# P1R3.net
KiCad netlist of a schematic drawn in EAGLE
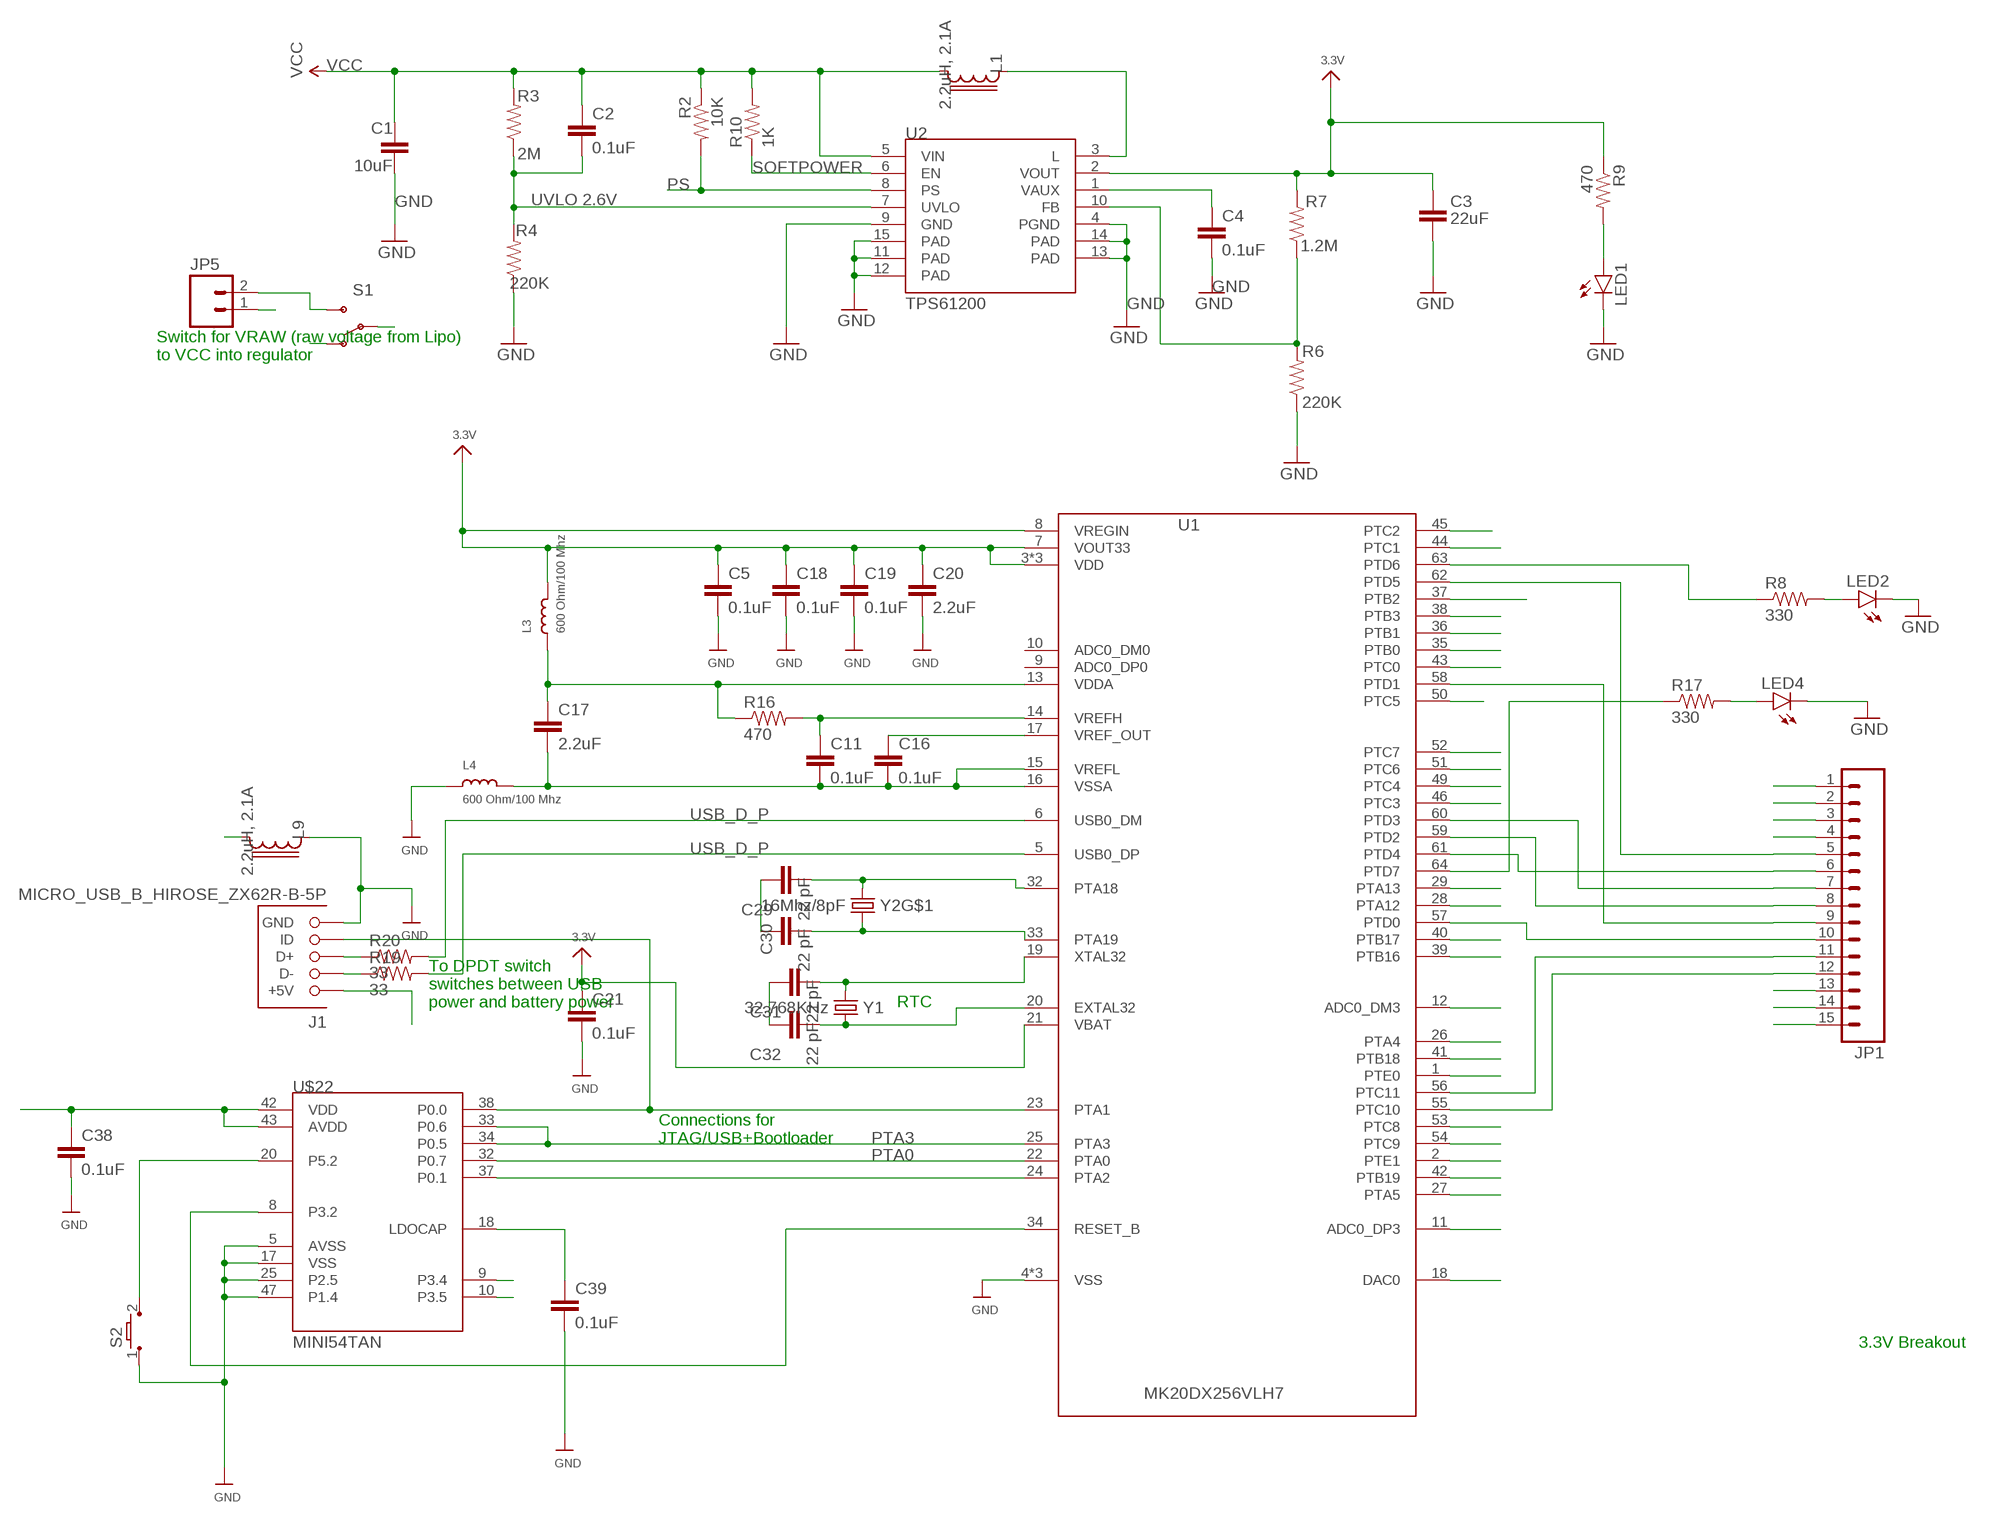
[diagram p0: schematic, sheet 1]
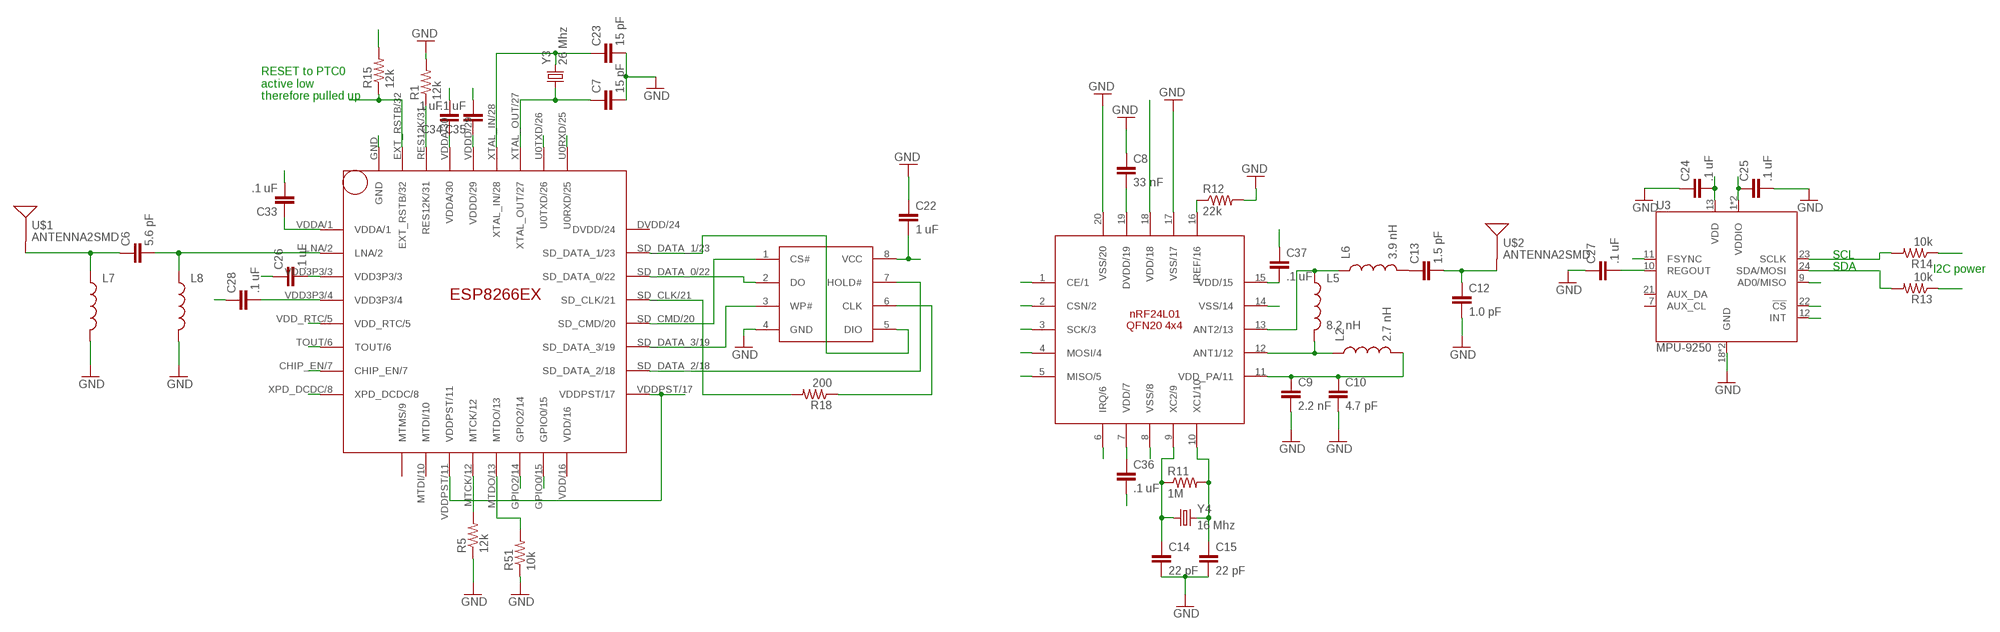
[diagram p1: schematic, sheet 2]

(export (version "E")
  (design (tool "Eeschema 10.0.6"))
  (components
    (comp (ref "C1")
      (value "10uF")
      (footprint "eagle-import:0603-CAP")
      (fields (field (name "MF") "Murata") (field (name "MPN") "GRM188R60J106ME47D"))
      (libsource (lib "eagle-import") (part "CAPACITOR-10UF"))
    )
    (comp (ref "C2")
      (value "0.1uF")
      (footprint "eagle-import:0603-CAP")
      (fields (field (name "MF") "Kemet") (field (name "MPN") "C0603C104J3RACTU"))
      (libsource (lib "eagle-import") (part "CAPACITOR-0.1UF"))
    )
    (comp (ref "C3")
      (value "22uF")
      (footprint "eagle-import:0603-CAP")
      (fields (field (name "MF") "Murata") (field (name "MPN") "GRM188R60J226MEA0D"))
      (libsource (lib "eagle-import") (part "CAPACITOR-22UF"))
    )
    (comp (ref "C4")
      (value "0.1uF")
      (footprint "eagle-import:0603-CAP")
      (fields (field (name "MF") "Kemet") (field (name "MPN") "C0603C104J3RACTU"))
      (libsource (lib "eagle-import") (part "CAPACITOR-0.1UF"))
    )
    (comp (ref "C5")
      (value "0.1uF")
      (footprint "eagle-import:0603-CAP")
      (fields (field (name "MF") "Kemet") (field (name "MPN") "C0603C104J3RACTU"))
      (libsource (lib "eagle-import") (part "CAPACITOR-0.1UF"))
    )
    (comp (ref "C11")
      (value "0.1uF")
      (footprint "eagle-import:0603-CAP")
      (fields (field (name "MF") "Kemet") (field (name "MPN") "C0603C104J3RACTU"))
      (libsource (lib "eagle-import") (part "CAPACITOR-0.1UF"))
    )
    (comp (ref "C16")
      (value "0.1uF")
      (footprint "eagle-import:0603-CAP")
      (fields (field (name "MF") "Kemet") (field (name "MPN") "C0603C104J3RACTU"))
      (libsource (lib "eagle-import") (part "CAPACITOR-0.1UF"))
    )
    (comp (ref "C17")
      (value "2.2uF")
      (footprint "eagle-import:0603-CAP")
      (fields (field (name "MF") "Kemet") (field (name "MPN") "C0603C225K4PACTU"))
      (libsource (lib "eagle-import") (part "CAPACITOR-2.2UF"))
    )
    (comp (ref "C18")
      (value "0.1uF")
      (footprint "eagle-import:0603-CAP")
      (fields (field (name "MF") "Kemet") (field (name "MPN") "C0603C104J3RACTU"))
      (libsource (lib "eagle-import") (part "CAPACITOR-0.1UF"))
    )
    (comp (ref "C19")
      (value "0.1uF")
      (footprint "eagle-import:0603-CAP")
      (fields (field (name "MF") "Kemet") (field (name "MPN") "C0603C104J3RACTU"))
      (libsource (lib "eagle-import") (part "CAPACITOR-0.1UF"))
    )
    (comp (ref "C20")
      (value "2.2uF")
      (footprint "eagle-import:0603-CAP")
      (fields (field (name "MF") "Kemet") (field (name "MPN") "C0603C225K4PACTU"))
      (libsource (lib "eagle-import") (part "CAPACITOR-2.2UF"))
    )
    (comp (ref "C21")
      (value "0.1uF")
      (footprint "eagle-import:0603-CAP")
      (fields (field (name "MF") "Kemet") (field (name "MPN") "C0603C104J3RACTU"))
      (libsource (lib "eagle-import") (part "CAPACITOR-0.1UF"))
    )
    (comp (ref "C29")
      (value "22 pF")
      (footprint "eagle-import:0603-CAP")
      (fields (field (name "MF") "Murata") (field (name "MPN") "GRM188R60J106ME47D"))
      (libsource (lib "eagle-import") (part "CAPACITOR-10UF"))
    )
    (comp (ref "C30")
      (value "22 pF")
      (footprint "eagle-import:0603-CAP")
      (fields (field (name "MF") "Murata") (field (name "MPN") "GRM188R60J106ME47D"))
      (libsource (lib "eagle-import") (part "CAPACITOR-10UF"))
    )
    (comp (ref "C31")
      (value "22 pF")
      (footprint "eagle-import:0603-CAP")
      (fields (field (name "MF") "Murata") (field (name "MPN") "GRM188R60J106ME47D"))
      (libsource (lib "eagle-import") (part "CAPACITOR-10UF"))
    )
    (comp (ref "C32")
      (value "22 pF")
      (footprint "eagle-import:0603-CAP")
      (fields (field (name "MF") "Murata") (field (name "MPN") "GRM188R60J106ME47D"))
      (libsource (lib "eagle-import") (part "CAPACITOR-10UF"))
    )
    (comp (ref "C38")
      (value "0.1uF")
      (footprint "eagle-import:0603-CAP")
      (fields (field (name "MF") "Kemet") (field (name "MPN") "C0603C104J3RACTU"))
      (libsource (lib "eagle-import") (part "CAPACITOR-0.1UF"))
    )
    (comp (ref "C39")
      (value "0.1uF")
      (footprint "eagle-import:0603-CAP")
      (fields (field (name "MF") "Kemet") (field (name "MPN") "C0603C104J3RACTU"))
      (libsource (lib "eagle-import") (part "CAPACITOR-0.1UF"))
    )
    (comp (ref "J1")
      (value "MICRO_USB_B_HIROSE_ZX62R-B-5P")
      (footprint "eagle-import:USB_MICRO_B-HIROSE-ZX62R-B-5P")
      (libsource (lib "eagle-import") (part "MICRO_USB_B_HIROSE_ZX62R-B-5P"))
    )
    (comp (ref "JP1")
      (value "M15")
      (footprint "eagle-import:1X15")
      (libsource (lib "eagle-import") (part "M15"))
    )
    (comp (ref "JP5")
      (value "M02PTH")
      (footprint "eagle-import:1X02")
      (libsource (lib "eagle-import") (part "M02PTH"))
    )
    (comp (ref "L1")
      (value "2.2uH, 2.1A")
      (footprint "eagle-import:LPS3015")
      (fields (field (name "MF") "Coilcraft") (field (name "MPN") "LPS3015-222MRB"))
      (libsource (lib "eagle-import") (part "LPS30152.2UH"))
    )
    (comp (ref "L3")
      (value "600 Ohm/100 Mhz")
      (footprint "eagle-import:0805")
      (fields (field (name "MF") "Taiyo Yuden") (field (name "MPN") "BK2125HM601-T"))
      (libsource (lib "eagle-import") (part "INDUCTOR-BK2125HM601-T"))
    )
    (comp (ref "L4")
      (value "600 Ohm/100 Mhz")
      (footprint "eagle-import:0805")
      (fields (field (name "MF") "Taiyo Yuden") (field (name "MPN") "BK2125HM601-T"))
      (libsource (lib "eagle-import") (part "INDUCTOR-BK2125HM601-T"))
    )
    (comp (ref "L9")
      (value "2.2uH, 2.1A")
      (footprint "eagle-import:LPS3015")
      (fields (field (name "MF") "Coilcraft") (field (name "MPN") "LPS3015-222MRB"))
      (libsource (lib "eagle-import") (part "LPS30152.2UH"))
    )
    (comp (ref "LED1")
      (value "LED-GREEN")
      (footprint "eagle-import:LED-0603")
      (fields (field (name "MF") "Avago") (field (name "MPN") "HSMG-C190"))
      (libsource (lib "eagle-import") (part "LED-GREEN"))
    )
    (comp (ref "LED2")
      (value "LED-GREEN")
      (footprint "eagle-import:LED-0603")
      (fields (field (name "MF") "Avago") (field (name "MPN") "HSMG-C190"))
      (libsource (lib "eagle-import") (part "LED-GREEN"))
    )
    (comp (ref "LED4")
      (value "LED-GREEN")
      (footprint "eagle-import:LED-0603")
      (fields (field (name "MF") "Avago") (field (name "MPN") "HSMG-C190"))
      (libsource (lib "eagle-import") (part "LED-GREEN"))
    )
    (comp (ref "R2")
      (value "10K")
      (footprint "eagle-import:0603-RES")
      (fields (field (name "MF") "Panasonic") (field (name "MPN") "ERJ-3GEYJ103V"))
      (libsource (lib "eagle-import") (part "RESISTOR-10K"))
    )
    (comp (ref "R3")
      (value "2M")
      (footprint "eagle-import:0603-RES")
      (fields (field (name "MF") "Panasonic") (field (name "MPN") "ERJ-3GEYJ205V"))
      (libsource (lib "eagle-import") (part "RESISTOR-2M"))
    )
    (comp (ref "R4")
      (value "220K")
      (footprint "eagle-import:0603-RES")
      (fields (field (name "MF") "Panasonic") (field (name "MPN") "ERJ-3GEYJ224V"))
      (libsource (lib "eagle-import") (part "RESISTOR-220K"))
    )
    (comp (ref "R6")
      (value "220K")
      (footprint "eagle-import:0603-RES")
      (fields (field (name "MF") "Panasonic") (field (name "MPN") "ERJ-3GEYJ224V"))
      (libsource (lib "eagle-import") (part "RESISTOR-220K"))
    )
    (comp (ref "R7")
      (value "1.2M")
      (footprint "eagle-import:0603-RES")
      (fields (field (name "MF") "Panasonic") (field (name "MPN") "ERJ-3GEYJ125V"))
      (libsource (lib "eagle-import") (part "RESISTOR-1.2M"))
    )
    (comp (ref "R8")
      (value "330")
      (footprint "eagle-import:0603-RES")
      (fields (field (name "MF") "Panasonic") (field (name "MPN") "ERJ-3GEYJ471V"))
      (libsource (lib "eagle-import") (part "RESISTOR-470"))
    )
    (comp (ref "R9")
      (value "470")
      (footprint "eagle-import:0603-RES")
      (fields (field (name "MF") "Panasonic") (field (name "MPN") "ERJ-3GEYJ471V"))
      (libsource (lib "eagle-import") (part "RESISTOR-470"))
    )
    (comp (ref "R10")
      (value "1K")
      (footprint "eagle-import:0603-RES")
      (fields (field (name "MF") "Panasonic") (field (name "MPN") "ERJ-3GEYJ102V"))
      (libsource (lib "eagle-import") (part "RESISTOR-1K"))
    )
    (comp (ref "R16")
      (value "470")
      (footprint "eagle-import:0603-RES")
      (fields (field (name "MF") "Panasonic") (field (name "MPN") "ERJ-3GEYJ471V"))
      (libsource (lib "eagle-import") (part "RESISTOR-470"))
    )
    (comp (ref "R17")
      (value "330")
      (footprint "eagle-import:0603-RES")
      (fields (field (name "MF") "Panasonic") (field (name "MPN") "ERJ-3GEYJ471V"))
      (libsource (lib "eagle-import") (part "RESISTOR-470"))
    )
    (comp (ref "R19")
      (value "33")
      (footprint "eagle-import:0402-RES")
      (libsource (lib "eagle-import") (part "RESISTOR0402-RES"))
    )
    (comp (ref "R20")
      (value "33")
      (footprint "eagle-import:0402-RES")
      (libsource (lib "eagle-import") (part "RESISTOR0402-RES"))
    )
    (comp (ref "S1")
      (value "SWITCH-SPDT-SMD-A")
      (footprint "eagle-import:SWITCH-SPST-SMD-A")
      (libsource (lib "eagle-import") (part "SWITCH-SPDT-SMD-A"))
    )
    (comp (ref "S2")
      (value "TL3302-G")
      (footprint "eagle-import:TL3302_GULL_WING")
      (libsource (lib "eagle-import") (part "TL3302-G"))
    )
    (comp (ref "U$22")
      (value "MINI54TAN")
      (footprint "eagle-import:MINI54TAN")
      (libsource (lib "eagle-import") (part "MINI54TAN"))
    )
    (comp (ref "U1")
      (value "MK20DX256VLH7")
      (footprint "eagle-import:MK20DX256VLH7")
      (fields (field (name "MF") "Freescale"))
      (libsource (lib "eagle-import") (part "MK20DX256VLH7"))
    )
    (comp (ref "U2")
      (value "TPS61200")
      (footprint "eagle-import:QFN-10_PAD")
      (fields (field (name "MF") "Texas Instruments") (field (name "MPN") "TPS61200DRCR"))
      (libsource (lib "eagle-import") (part "TPS61200"))
    )
    (comp (ref "Y1")
      (value "32.768KHz")
      (footprint "eagle-import:CRYSTAL-TXC-7A")
      (fields (field (name "MF") "Epson Timing") (field (name "MPN") "FC-255 32.7680K-A3"))
      (libsource (lib "eagle-import") (part "CRYSTAL/32.768KHZ/SMD-TXC_7A"))
    )
    (comp (ref "Y2")
      (value "16Mhz/8pF")
      (footprint "eagle-import:CRYSTAL-SMD-5X3")
      (fields (field (name "MF") "ECS") (field (name "MPN") "ECS-160-8-30B-CKM"))
      (libsource (lib "eagle-import") (part "CRYSTAL/SMD-5X3-GND16MHZ/8PF"))
    )
    (comp (ref "C6")
      (value "5.6 pF")
      (footprint "eagle-import:0603-CAP")
      (libsource (lib "eagle-import") (part "CAP0603-CAP"))
    )
    (comp (ref "C7")
      (value "15 pF")
      (footprint "eagle-import:0603-CAP")
      (libsource (lib "eagle-import") (part "CAP0603-CAP"))
    )
    (comp (ref "C8")
      (value "33 nF")
      (footprint "eagle-import:0603-CAP")
      (libsource (lib "eagle-import") (part "CAP0603-CAP"))
    )
    (comp (ref "C9")
      (value "2.2 nF")
      (footprint "eagle-import:0603-CAP")
      (libsource (lib "eagle-import") (part "CAP0603-CAP"))
    )
    (comp (ref "C10")
      (value "4.7 pF")
      (footprint "eagle-import:0603-CAP")
      (libsource (lib "eagle-import") (part "CAP0603-CAP"))
    )
    (comp (ref "C12")
      (value "1.0 pF")
      (footprint "eagle-import:0603-CAP")
      (libsource (lib "eagle-import") (part "CAP0603-CAP"))
    )
    (comp (ref "C13")
      (value "1.5 pF")
      (footprint "eagle-import:0603-CAP")
      (libsource (lib "eagle-import") (part "CAP0603-CAP"))
    )
    (comp (ref "C14")
      (value "22 pF")
      (footprint "eagle-import:0603-CAP")
      (libsource (lib "eagle-import") (part "CAP0603-CAP"))
    )
    (comp (ref "C15")
      (value "22 pF")
      (footprint "eagle-import:0603-CAP")
      (libsource (lib "eagle-import") (part "CAP0603-CAP"))
    )
    (comp (ref "C22")
      (value "1 uF")
      (footprint "eagle-import:0603-CAP")
      (libsource (lib "eagle-import") (part "CAP0603-CAP"))
    )
    (comp (ref "C23")
      (value "15 pF")
      (footprint "eagle-import:0603-CAP")
      (libsource (lib "eagle-import") (part "CAP0603-CAP"))
    )
    (comp (ref "C24")
      (value ".1 uF")
      (footprint "eagle-import:0603-CAP")
      (libsource (lib "eagle-import") (part "CAP0603-CAP"))
    )
    (comp (ref "C25")
      (value ".1 uF")
      (footprint "eagle-import:0603-CAP")
      (libsource (lib "eagle-import") (part "CAP0603-CAP"))
    )
    (comp (ref "C26")
      (value ".1 uF")
      (footprint "eagle-import:0603-CAP")
      (libsource (lib "eagle-import") (part "CAP0603-CAP"))
    )
    (comp (ref "C27")
      (value ".1 uF")
      (footprint "eagle-import:0603-CAP")
      (libsource (lib "eagle-import") (part "CAP0603-CAP"))
    )
    (comp (ref "C28")
      (value ".1 uF")
      (footprint "eagle-import:0603-CAP")
      (libsource (lib "eagle-import") (part "CAP0603-CAP"))
    )
    (comp (ref "C33")
      (value ".1 uF")
      (footprint "eagle-import:0603-CAP")
      (libsource (lib "eagle-import") (part "CAP0603-CAP"))
    )
    (comp (ref "C34")
      (value ".1 uF")
      (footprint "eagle-import:0603-CAP")
      (libsource (lib "eagle-import") (part "CAP0603-CAP"))
    )
    (comp (ref "C35")
      (value ".1 uF")
      (footprint "eagle-import:0603-CAP")
      (libsource (lib "eagle-import") (part "CAP0603-CAP"))
    )
    (comp (ref "C36")
      (value ".1 uF")
      (footprint "eagle-import:0603-CAP")
      (libsource (lib "eagle-import") (part "CAP0603-CAP"))
    )
    (comp (ref "C37")
      (value ".1 uF")
      (footprint "eagle-import:0603-CAP")
      (libsource (lib "eagle-import") (part "CAP0603-CAP"))
    )
    (comp (ref "L2")
      (value "2.7 nH")
      (footprint "eagle-import:C0402")
      (libsource (lib "eagle-import") (part "INDUCTOR0402"))
    )
    (comp (ref "L5")
      (value "8.2 nH")
      (footprint "eagle-import:C0402")
      (libsource (lib "eagle-import") (part "INDUCTOR0402"))
    )
    (comp (ref "L6")
      (value "3.9 nH")
      (footprint "eagle-import:C0402")
      (libsource (lib "eagle-import") (part "INDUCTOR0402"))
    )
    (comp (ref "L7")
      (value "INDUCTOR30OHM,1.8A")
      (footprint "eagle-import:0603")
      (libsource (lib "eagle-import") (part "INDUCTOR30OHM,1.8A"))
    )
    (comp (ref "L8")
      (value "INDUCTOR30OHM,1.8A")
      (footprint "eagle-import:0603")
      (libsource (lib "eagle-import") (part "INDUCTOR30OHM,1.8A"))
    )
    (comp (ref "R1")
      (value "12k")
      (footprint "eagle-import:0603-RES")
      (libsource (lib "eagle-import") (part "SparkFun-Resistors_RESISTOR0603-RES"))
    )
    (comp (ref "R5")
      (value "12k")
      (footprint "eagle-import:0603-RES")
      (libsource (lib "eagle-import") (part "SparkFun-Resistors_RESISTOR0603-RES"))
    )
    (comp (ref "R11")
      (value "1M")
      (footprint "eagle-import:0603-RES")
      (libsource (lib "eagle-import") (part "SparkFun-Resistors_RESISTOR0603-RES"))
    )
    (comp (ref "R12")
      (value "22k")
      (footprint "eagle-import:0603-RES")
      (libsource (lib "eagle-import") (part "SparkFun-Resistors_RESISTOR0603-RES"))
    )
    (comp (ref "R13")
      (value "10k")
      (footprint "eagle-import:0603-RES")
      (libsource (lib "eagle-import") (part "SparkFun-Resistors_RESISTOR0603-RES"))
    )
    (comp (ref "R14")
      (value "10k")
      (footprint "eagle-import:0603-RES")
      (libsource (lib "eagle-import") (part "SparkFun-Resistors_RESISTOR0603-RES"))
    )
    (comp (ref "R15")
      (value "12k")
      (footprint "eagle-import:0603-RES")
      (libsource (lib "eagle-import") (part "SparkFun-Resistors_RESISTOR0603-RES"))
    )
    (comp (ref "R18")
      (value "200")
      (footprint "eagle-import:0603-RES")
      (libsource (lib "eagle-import") (part "SparkFun-Resistors_RESISTOR0603-RES"))
    )
    (comp (ref "R51")
      (value "10k")
      (footprint "eagle-import:0603-RES")
      (libsource (lib "eagle-import") (part "SparkFun-Resistors_RESISTOR0603-RES"))
    )
    (comp (ref "U$1")
      (value "ANTENNA2SMD")
      (footprint "eagle-import:ANTENNA-CHIP2")
      (libsource (lib "eagle-import") (part "ANTENNA2SMD"))
    )
    (comp (ref "U$2")
      (value "ANTENNA2SMD")
      (footprint "eagle-import:ANTENNA-CHIP2")
      (libsource (lib "eagle-import") (part "ANTENNA2SMD"))
    )
    (comp (ref "U$3")
      (value "25Q40")
      (footprint "eagle-import:SOP8")
      (libsource (lib "eagle-import") (part "25Q40"))
    )
    (comp (ref "U$4")
      (value "NRF24L01")
      (footprint "eagle-import:QFN20(4X4)")
      (libsource (lib "eagle-import") (part "NRF24L01"))
    )
    (comp (ref "U$6")
      (value "ESP8266EX")
      (footprint "eagle-import:QFN32")
      (libsource (lib "eagle-import") (part "ESP8266EX"))
    )
    (comp (ref "U3")
      (value "MPU-9250")
      (footprint "eagle-import:QFN-24_3MM")
      (libsource (lib "eagle-import") (part "MPU-9250"))
    )
    (comp (ref "Y3")
      (value "26 Mhz")
      (footprint "eagle-import:CRYSTAL-SMD-5X3")
      (libsource (lib "eagle-import") (part "CRYSTAL5X3"))
    )
    (comp (ref "Y4")
      (value "16 Mhz")
      (footprint "eagle-import:CRYSTAL-SMD-5X3")
      (libsource (lib "eagle-import") (part "CRYSTAL5X3"))
    )
  )
  (nets
    (net (code "1") (name "3.3V") (class "Default")
      (node (ref "C18") (pin "1") (pinfunction "1_1") (pintype "passive"))
      (node (ref "C19") (pin "1") (pinfunction "1_1") (pintype "passive"))
      (node (ref "C20") (pin "1") (pinfunction "1_1") (pintype "passive"))
      (node (ref "C21") (pin "1") (pinfunction "1_1") (pintype "passive"))
      (node (ref "C22") (pin "2") (pinfunction "2_2") (pintype "passive"))
      (node (ref "C24") (pin "2") (pinfunction "2_2") (pintype "passive"))
      (node (ref "C25") (pin "1") (pinfunction "1_1") (pintype "passive"))
      (node (ref "C26") (pin "2") (pinfunction "2_2") (pintype "passive"))
      (node (ref "C28") (pin "2") (pinfunction "2_2") (pintype "passive"))
      (node (ref "C3") (pin "1") (pinfunction "1_1") (pintype "passive"))
      (node (ref "C33") (pin "1") (pinfunction "1_1") (pintype "passive"))
      (node (ref "C34") (pin "1") (pinfunction "1_1") (pintype "passive"))
      (node (ref "C35") (pin "1") (pinfunction "1_1") (pintype "passive"))
      (node (ref "C36") (pin "1") (pinfunction "1_1") (pintype "passive"))
      (node (ref "C37") (pin "2") (pinfunction "2_2") (pintype "passive"))
      (node (ref "C38") (pin "1") (pinfunction "1_1") (pintype "passive"))
      (node (ref "C5") (pin "1") (pinfunction "1_1") (pintype "passive"))
      (node (ref "JP1") (pin "13") (pinfunction "13_13") (pintype "passive"))
      (node (ref "JP1") (pin "14") (pinfunction "14_14") (pintype "passive"))
      (node (ref "JP1") (pin "15") (pinfunction "15_15") (pintype "passive"))
      (node (ref "L3") (pin "2") (pinfunction "2_2") (pintype "passive"))
      (node (ref "R13") (pin "1") (pinfunction "1_1") (pintype "passive"))
      (node (ref "R14") (pin "1") (pinfunction "1_1") (pintype "passive"))
      (node (ref "R15") (pin "2") (pinfunction "2_2") (pintype "passive"))
      (node (ref "R7") (pin "2") (pinfunction "2_2") (pintype "passive"))
      (node (ref "R9") (pin "1") (pinfunction "1_1") (pintype "passive"))
      (node (ref "U$22") (pin "42") (pinfunction "VDD_42") (pintype "bidirectional"))
      (node (ref "U$22") (pin "43") (pinfunction "AVDD_43") (pintype "bidirectional"))
      (node (ref "U$3") (pin "8") (pinfunction "VCC_8") (pintype "bidirectional"))
      (node (ref "U$4") (pin "15") (pinfunction "VDD/15_15") (pintype "bidirectional"))
      (node (ref "U$4") (pin "18") (pinfunction "VDD/18_18") (pintype "bidirectional"))
      (node (ref "U$4") (pin "7") (pinfunction "VDD/7_7") (pintype "bidirectional"))
      (node (ref "U$6") (pin "VDD3P3/3") (pinfunction "VDD3P3/3_VDD3P3/3") (pintype "bidirectional"))
      (node (ref "U$6") (pin "VDD3P3/4") (pinfunction "VDD3P3/4_VDD3P3/4") (pintype "bidirectional"))
      (node (ref "U$6") (pin "VDDA/1") (pinfunction "VDDA/1_VDDA/1") (pintype "bidirectional"))
      (node (ref "U$6") (pin "VDDA/30") (pinfunction "VDDA/30_VDDA/30") (pintype "bidirectional"))
      (node (ref "U$6") (pin "VDDD/29") (pinfunction "VDDD/29_VDDD/29") (pintype "bidirectional"))
      (node (ref "U$6") (pin "VDDPST/11") (pinfunction "VDDPST/11_VDDPST/11") (pintype "bidirectional"))
      (node (ref "U$6") (pin "VDDPST/17") (pinfunction "VDDPST/17_VDDPST/17") (pintype "bidirectional"))
      (node (ref "U1") (pin "21") (pinfunction "VBAT_21") (pintype "bidirectional"))
      (node (ref "U1") (pin "3") (pinfunction "VDD_3") (pintype "bidirectional"))
      (node (ref "U1") (pin "30") (pinfunction "VDD_30") (pintype "bidirectional"))
      (node (ref "U1") (pin "48") (pinfunction "VDD_48") (pintype "bidirectional"))
      (node (ref "U1") (pin "7") (pinfunction "VOUT33_7") (pintype "bidirectional"))
      (node (ref "U1") (pin "8") (pinfunction "VREGIN_8") (pintype "bidirectional"))
      (node (ref "U2") (pin "2") (pinfunction "VOUT_2") (pintype "passive"))
      (node (ref "U3") (pin "1") (pinfunction "VDDIO_1") (pintype "bidirectional"))
      (node (ref "U3") (pin "13") (pinfunction "VDD_13") (pintype "bidirectional"))
      (node (ref "U3") (pin "22") (pinfunction "~{CS}_22") (pintype "bidirectional"))
      (node (ref "U3") (pin "8") (pinfunction "VDDIO_8") (pintype "bidirectional"))
    )
    (net (code "2") (name "AD0") (class "Default")
      (node (ref "U1") (pin "45") (pinfunction "PTC2_45") (pintype "bidirectional"))
      (node (ref "U3") (pin "9") (pinfunction "AD0/MISO_9") (pintype "bidirectional"))
    )
    (net (code "3") (name "GND") (class "Default")
      (node (ref "C1") (pin "2") (pinfunction "2_2") (pintype "passive"))
      (node (ref "C10") (pin "2") (pinfunction "2_2") (pintype "passive"))
      (node (ref "C12") (pin "2") (pinfunction "2_2") (pintype "passive"))
      (node (ref "C14") (pin "2") (pinfunction "2_2") (pintype "passive"))
      (node (ref "C15") (pin "2") (pinfunction "2_2") (pintype "passive"))
      (node (ref "C18") (pin "2") (pinfunction "2_2") (pintype "passive"))
      (node (ref "C19") (pin "2") (pinfunction "2_2") (pintype "passive"))
      (node (ref "C20") (pin "2") (pinfunction "2_2") (pintype "passive"))
      (node (ref "C21") (pin "2") (pinfunction "2_2") (pintype "passive"))
      (node (ref "C22") (pin "1") (pinfunction "1_1") (pintype "passive"))
      (node (ref "C23") (pin "2") (pinfunction "2_2") (pintype "passive"))
      (node (ref "C24") (pin "1") (pinfunction "1_1") (pintype "passive"))
      (node (ref "C25") (pin "2") (pinfunction "2_2") (pintype "passive"))
      (node (ref "C26") (pin "1") (pinfunction "1_1") (pintype "passive"))
      (node (ref "C27") (pin "1") (pinfunction "1_1") (pintype "passive"))
      (node (ref "C28") (pin "1") (pinfunction "1_1") (pintype "passive"))
      (node (ref "C29") (pin "1") (pinfunction "1_1") (pintype "passive"))
      (node (ref "C3") (pin "2") (pinfunction "2_2") (pintype "passive"))
      (node (ref "C30") (pin "1") (pinfunction "1_1") (pintype "passive"))
      (node (ref "C31") (pin "1") (pinfunction "1_1") (pintype "passive"))
      (node (ref "C32") (pin "1") (pinfunction "1_1") (pintype "passive"))
      (node (ref "C33") (pin "2") (pinfunction "2_2") (pintype "passive"))
      (node (ref "C34") (pin "2") (pinfunction "2_2") (pintype "passive"))
      (node (ref "C35") (pin "2") (pinfunction "2_2") (pintype "passive"))
      (node (ref "C36") (pin "2") (pinfunction "2_2") (pintype "passive"))
      (node (ref "C37") (pin "1") (pinfunction "1_1") (pintype "passive"))
      (node (ref "C38") (pin "2") (pinfunction "2_2") (pintype "passive"))
      (node (ref "C39") (pin "2") (pinfunction "2_2") (pintype "passive"))
      (node (ref "C4") (pin "2") (pinfunction "2_2") (pintype "passive"))
      (node (ref "C5") (pin "2") (pinfunction "2_2") (pintype "passive"))
      (node (ref "C7") (pin "2") (pinfunction "2_2") (pintype "passive"))
      (node (ref "C8") (pin "1") (pinfunction "1_1") (pintype "passive"))
      (node (ref "C9") (pin "2") (pinfunction "2_2") (pintype "passive"))
      (node (ref "J1") (pin "5") (pinfunction "GND_5") (pintype "bidirectional"))
      (node (ref "JP1") (pin "1") (pinfunction "1_1") (pintype "passive"))
      (node (ref "JP1") (pin "2") (pinfunction "2_2") (pintype "passive"))
      (node (ref "JP1") (pin "3") (pinfunction "3_3") (pintype "passive"))
      (node (ref "JP1") (pin "4") (pinfunction "4_4") (pintype "passive"))
      (node (ref "JP5") (pin "1") (pinfunction "1_1") (pintype "passive"))
      (node (ref "L4") (pin "1") (pinfunction "1_1") (pintype "passive"))
      (node (ref "L7") (pin "2") (pinfunction "2_2") (pintype "passive"))
      (node (ref "L8") (pin "2") (pinfunction "2_2") (pintype "passive"))
      (node (ref "L9") (pin "1") (pinfunction "1_1") (pintype "passive"))
      (node (ref "LED1") (pin "C") (pinfunction "C_C") (pintype "passive"))
      (node (ref "LED2") (pin "C") (pinfunction "C_C") (pintype "passive"))
      (node (ref "LED4") (pin "C") (pinfunction "C_C") (pintype "passive"))
      (node (ref "R1") (pin "2") (pinfunction "2_2") (pintype "passive"))
      (node (ref "R12") (pin "2") (pinfunction "2_2") (pintype "passive"))
      (node (ref "R4") (pin "1") (pinfunction "1_1") (pintype "passive"))
      (node (ref "R5") (pin "1") (pinfunction "1_1") (pintype "passive"))
      (node (ref "R51") (pin "1") (pinfunction "1_1") (pintype "passive"))
      (node (ref "R6") (pin "1") (pinfunction "1_1") (pintype "passive"))
      (node (ref "S2") (pin "1") (pinfunction "1_1") (pintype "passive"))
      (node (ref "U$22") (pin "17") (pinfunction "VSS_17") (pintype "bidirectional"))
      (node (ref "U$22") (pin "25") (pinfunction "P2.5_25") (pintype "bidirectional"))
      (node (ref "U$22") (pin "47") (pinfunction "P1.4_47") (pintype "bidirectional"))
      (node (ref "U$22") (pin "5") (pinfunction "AVSS_5") (pintype "bidirectional"))
      (node (ref "U$3") (pin "4") (pinfunction "GND_4") (pintype "bidirectional"))
      (node (ref "U$4") (pin "14") (pinfunction "VSS/14_14") (pintype "bidirectional"))
      (node (ref "U$4") (pin "17") (pinfunction "VSS/17_17") (pintype "bidirectional"))
      (node (ref "U$4") (pin "20") (pinfunction "VSS/20_20") (pintype "bidirectional"))
      (node (ref "U$4") (pin "8") (pinfunction "VSS/8_8") (pintype "bidirectional"))
      (node (ref "U$6") (pin "GND") (pinfunction "GND_GND") (pintype "bidirectional"))
      (node (ref "U1") (pin "31") (pinfunction "VSS_31") (pintype "bidirectional"))
      (node (ref "U1") (pin "4") (pinfunction "VSS_4") (pintype "bidirectional"))
      (node (ref "U1") (pin "47") (pinfunction "VSS_47") (pintype "bidirectional"))
      (node (ref "U2") (pin "11") (pinfunction "PAD_11") (pintype "power_in"))
      (node (ref "U2") (pin "12") (pinfunction "PAD_12") (pintype "power_in"))
      (node (ref "U2") (pin "13") (pinfunction "PAD_13") (pintype "power_in"))
      (node (ref "U2") (pin "14") (pinfunction "PAD_14") (pintype "power_in"))
      (node (ref "U2") (pin "15") (pinfunction "PAD_15") (pintype "power_in"))
      (node (ref "U2") (pin "4") (pinfunction "PGND_4") (pintype "power_in"))
      (node (ref "U2") (pin "9") (pinfunction "GND_9") (pintype "power_in"))
      (node (ref "U3") (pin "18") (pinfunction "GND_18") (pintype "bidirectional"))
      (node (ref "U3") (pin "20") (pinfunction "GND_20") (pintype "bidirectional"))
    )
    (net (code "4") (name "Net-(C6-Pad2)") (class "Default")
      (node (ref "C6") (pin "2") (pinfunction "2_2") (pintype "passive"))
      (node (ref "L8") (pin "1") (pinfunction "1_1") (pintype "passive"))
      (node (ref "U$6") (pin "LNA/2") (pinfunction "LNA/2_LNA/2") (pintype "bidirectional"))
    )
    (net (code "5") (name "Net-(C7-Pad1)") (class "Default")
      (node (ref "C7") (pin "1") (pinfunction "1_1") (pintype "passive"))
      (node (ref "U$6") (pin "XTAL_OUT/27") (pinfunction "XTAL_OUT/27_XTAL_OUT/27") (pintype "bidirectional"))
      (node (ref "Y3") (pin "1") (pinfunction "1_1") (pintype "passive"))
    )
    (net (code "6") (name "Net-(C13-Pad1)") (class "Default")
      (node (ref "C13") (pin "1") (pinfunction "1_1") (pintype "passive"))
      (node (ref "L6") (pin "2") (pinfunction "2_2") (pintype "passive"))
    )
    (net (code "7") (name "Net-(J1-D+)") (class "Default")
      (node (ref "J1") (pin "3") (pinfunction "D+_3") (pintype "bidirectional"))
      (node (ref "R20") (pin "1") (pinfunction "1_1") (pintype "passive"))
    )
    (net (code "8") (name "Net-(J1-D-)") (class "Default")
      (node (ref "J1") (pin "2") (pinfunction "D-_2") (pintype "bidirectional"))
      (node (ref "R19") (pin "1") (pinfunction "1_1") (pintype "passive"))
    )
    (net (code "9") (name "Net-(J1-ID)") (class "Default")
      (node (ref "J1") (pin "4") (pinfunction "ID_4") (pintype "bidirectional"))
      (node (ref "U$22") (pin "38") (pinfunction "P0.0_38") (pintype "bidirectional"))
      (node (ref "U1") (pin "23") (pinfunction "PTA1_23") (pintype "bidirectional"))
    )
    (net (code "10") (name "Net-(LED1-PadA)") (class "Default")
      (node (ref "LED1") (pin "A") (pinfunction "A_A") (pintype "passive"))
      (node (ref "R9") (pin "2") (pinfunction "2_2") (pintype "passive"))
    )
    (net (code "11") (name "Net-(LED2-PadA)") (class "Default")
      (node (ref "LED2") (pin "A") (pinfunction "A_A") (pintype "passive"))
      (node (ref "R8") (pin "2") (pinfunction "2_2") (pintype "passive"))
    )
    (net (code "12") (name "Net-(LED4-PadA)") (class "Default")
      (node (ref "LED4") (pin "A") (pinfunction "A_A") (pintype "passive"))
      (node (ref "R17") (pin "2") (pinfunction "2_2") (pintype "passive"))
    )
    (net (code "13") (name "Net-(R1-Pad1)") (class "Default")
      (node (ref "R1") (pin "1") (pinfunction "1_1") (pintype "passive"))
      (node (ref "U$6") (pin "RES12K/31") (pinfunction "RES12K/31_RES12K/31") (pintype "bidirectional"))
    )
    (net (code "14") (name "Net-(R5-Pad2)") (class "Default")
      (node (ref "R5") (pin "2") (pinfunction "2_2") (pintype "passive"))
      (node (ref "U$6") (pin "MTCK/12") (pinfunction "MTCK/12_MTCK/12") (pintype "bidirectional"))
    )
    (net (code "15") (name "Net-(R18-Pad2)") (class "Default")
      (node (ref "R18") (pin "2") (pinfunction "2_2") (pintype "passive"))
      (node (ref "U$6") (pin "SD_CLK/21") (pinfunction "SD_CLK/21_SD_CLK/21") (pintype "bidirectional"))
    )
    (net (code "16") (name "Net-(R51-Pad2)") (class "Default")
      (node (ref "R51") (pin "2") (pinfunction "2_2") (pintype "passive"))
      (node (ref "U$6") (pin "MTDO/13") (pinfunction "MTDO/13_MTDO/13") (pintype "bidirectional"))
    )
    (net (code "17") (name "Net-(S1-S)") (class "Default")
      (node (ref "JP5") (pin "2") (pinfunction "2_2") (pintype "passive"))
      (node (ref "S1") (pin "3") (pinfunction "S_3") (pintype "passive"))
    )
    (net (code "18") (name "Net-(U$1-SIGNAL)") (class "Default")
      (node (ref "C6") (pin "1") (pinfunction "1_1") (pintype "passive"))
      (node (ref "L7") (pin "1") (pinfunction "1_1") (pintype "passive"))
      (node (ref "U$1") (pin "FEED") (pinfunction "SIGNAL_FEED") (pintype "bidirectional"))
    )
    (net (code "19") (name "Net-(U$2-SIGNAL)") (class "Default")
      (node (ref "C12") (pin "1") (pinfunction "1_1") (pintype "passive"))
      (node (ref "C13") (pin "2") (pinfunction "2_2") (pintype "passive"))
      (node (ref "U$2") (pin "FEED") (pinfunction "SIGNAL_FEED") (pintype "bidirectional"))
    )
    (net (code "20") (name "Net-(U$3-CLK)") (class "Default")
      (node (ref "R18") (pin "1") (pinfunction "1_1") (pintype "passive"))
      (node (ref "U$3") (pin "6") (pinfunction "CLK_6") (pintype "bidirectional"))
    )
    (net (code "21") (name "Net-(U$3-CS#)") (class "Default")
      (node (ref "U$3") (pin "1") (pinfunction "CS#_1") (pintype "bidirectional"))
      (node (ref "U$6") (pin "SD_CMD/20") (pinfunction "SD_CMD/20_SD_CMD/20") (pintype "bidirectional"))
    )
    (net (code "22") (name "Net-(U$3-DIO)") (class "Default")
      (node (ref "U$3") (pin "5") (pinfunction "DIO_5") (pintype "bidirectional"))
      (node (ref "U$6") (pin "SD_DATA_1/23") (pinfunction "SD_DATA_1/23_SD_DATA_1/23") (pintype "bidirectional"))
    )
    (net (code "23") (name "Net-(U$3-DO)") (class "Default")
      (node (ref "U$3") (pin "2") (pinfunction "DO_2") (pintype "bidirectional"))
      (node (ref "U$6") (pin "SD_DATA_0/22") (pinfunction "SD_DATA_0/22_SD_DATA_0/22") (pintype "bidirectional"))
    )
    (net (code "24") (name "Net-(U$3-HOLD#)") (class "Default")
      (node (ref "U$3") (pin "7") (pinfunction "HOLD#_7") (pintype "bidirectional"))
      (node (ref "U$6") (pin "SD_DATA_2/18") (pinfunction "SD_DATA_2/18_SD_DATA_2/18") (pintype "bidirectional"))
    )
    (net (code "25") (name "Net-(U$3-WP#)") (class "Default")
      (node (ref "U$3") (pin "3") (pinfunction "WP#_3") (pintype "bidirectional"))
      (node (ref "U$6") (pin "SD_DATA_3/19") (pinfunction "SD_DATA_3/19_SD_DATA_3/19") (pintype "bidirectional"))
    )
    (net (code "26") (name "Net-(U$4-ANT1{slash}12)") (class "Default")
      (node (ref "L2") (pin "1") (pinfunction "1_1") (pintype "passive"))
      (node (ref "L5") (pin "2") (pinfunction "2_2") (pintype "passive"))
      (node (ref "U$4") (pin "12") (pinfunction "ANT1/12_12") (pintype "bidirectional"))
    )
    (net (code "27") (name "Net-(U$4-ANT2{slash}13)") (class "Default")
      (node (ref "L5") (pin "1") (pinfunction "1_1") (pintype "passive"))
      (node (ref "L6") (pin "1") (pinfunction "1_1") (pintype "passive"))
      (node (ref "U$4") (pin "13") (pinfunction "ANT2/13_13") (pintype "bidirectional"))
    )
    (net (code "28") (name "Net-(U$4-DVDD{slash}19)") (class "Default")
      (node (ref "C8") (pin "2") (pinfunction "2_2") (pintype "passive"))
      (node (ref "U$4") (pin "19") (pinfunction "DVDD/19_19") (pintype "bidirectional"))
    )
    (net (code "29") (name "Net-(U$4-IREF{slash}16)") (class "Default")
      (node (ref "R12") (pin "1") (pinfunction "1_1") (pintype "passive"))
      (node (ref "U$4") (pin "16") (pinfunction "IREF/16_16") (pintype "bidirectional"))
    )
    (net (code "30") (name "Net-(U$4-VDD_PA{slash}11)") (class "Default")
      (node (ref "C10") (pin "1") (pinfunction "1_1") (pintype "passive"))
      (node (ref "C9") (pin "1") (pinfunction "1_1") (pintype "passive"))
      (node (ref "L2") (pin "2") (pinfunction "2_2") (pintype "passive"))
      (node (ref "U$4") (pin "11") (pinfunction "VDD_PA/11_11") (pintype "bidirectional"))
    )
    (net (code "31") (name "Net-(U$4-XC1{slash}10)") (class "Default")
      (node (ref "C15") (pin "1") (pinfunction "1_1") (pintype "passive"))
      (node (ref "R11") (pin "2") (pinfunction "2_2") (pintype "passive"))
      (node (ref "U$4") (pin "10") (pinfunction "XC1/10_10") (pintype "bidirectional"))
      (node (ref "Y4") (pin "3") (pinfunction "2_3") (pintype "passive"))
    )
    (net (code "32") (name "Net-(U$4-XC2{slash}9)") (class "Default")
      (node (ref "C14") (pin "1") (pinfunction "1_1") (pintype "passive"))
      (node (ref "R11") (pin "1") (pinfunction "1_1") (pintype "passive"))
      (node (ref "U$4") (pin "9") (pinfunction "XC2/9_9") (pintype "bidirectional"))
      (node (ref "Y4") (pin "1") (pinfunction "1_1") (pintype "passive"))
    )
    (net (code "33") (name "Net-(U$22-LDOCAP)") (class "Default")
      (node (ref "C39") (pin "1") (pinfunction "1_1") (pintype "passive"))
      (node (ref "U$22") (pin "18") (pinfunction "LDOCAP_18") (pintype "bidirectional"))
    )
    (net (code "34") (name "Net-(U$22-P0.1)") (class "Default")
      (node (ref "U$22") (pin "37") (pinfunction "P0.1_37") (pintype "bidirectional"))
      (node (ref "U1") (pin "24") (pinfunction "PTA2_24") (pintype "bidirectional"))
    )
    (net (code "35") (name "Net-(U$22-P3.2)") (class "Default")
      (node (ref "U$22") (pin "8") (pinfunction "P3.2_8") (pintype "bidirectional"))
      (node (ref "U1") (pin "34") (pinfunction "RESET_B_34") (pintype "bidirectional"))
    )
    (net (code "36") (name "Net-(U$22-P5.2)") (class "Default")
      (node (ref "S2") (pin "2") (pinfunction "2_2") (pintype "passive"))
      (node (ref "U$22") (pin "20") (pinfunction "P5.2_20") (pintype "bidirectional"))
    )
    (net (code "37") (name "Net-(U1-EXTAL32)") (class "Default")
      (node (ref "C32") (pin "2") (pinfunction "2_2") (pintype "passive"))
      (node (ref "U1") (pin "20") (pinfunction "EXTAL32_20") (pintype "bidirectional"))
      (node (ref "Y1") (pin "P$1") (pinfunction "1_P$1") (pintype "passive"))
    )
    (net (code "38") (name "Net-(U1-PTA18)") (class "Default")
      (node (ref "C29") (pin "2") (pinfunction "2_2") (pintype "passive"))
      (node (ref "U1") (pin "32") (pinfunction "PTA18_32") (pintype "bidirectional"))
      (node (ref "Y2") (pin "3") (pinfunction "2_3") (pintype "passive"))
    )
    (net (code "39") (name "Net-(U1-PTA19)") (class "Default")
      (node (ref "C30") (pin "2") (pinfunction "2_2") (pintype "passive"))
      (node (ref "U1") (pin "33") (pinfunction "PTA19_33") (pintype "bidirectional"))
      (node (ref "Y2") (pin "1") (pinfunction "1_1") (pintype "passive"))
    )
    (net (code "40") (name "Net-(U1-PTD6)") (class "Default")
      (node (ref "R8") (pin "1") (pinfunction "1_1") (pintype "passive"))
      (node (ref "U1") (pin "63") (pinfunction "PTD6_63") (pintype "bidirectional"))
    )
    (net (code "41") (name "Net-(U1-PTD7)") (class "Default")
      (node (ref "R17") (pin "1") (pinfunction "1_1") (pintype "passive"))
      (node (ref "U1") (pin "64") (pinfunction "PTD7_64") (pintype "bidirectional"))
    )
    (net (code "42") (name "Net-(U1-USB0_DP)") (class "Default")
      (node (ref "R19") (pin "2") (pinfunction "2_2") (pintype "passive"))
      (node (ref "U1") (pin "5") (pinfunction "USB0_DP_5") (pintype "bidirectional"))
    )
    (net (code "43") (name "Net-(U1-VDDA)") (class "Default")
      (node (ref "C17") (pin "1") (pinfunction "1_1") (pintype "passive"))
      (node (ref "L3") (pin "1") (pinfunction "1_1") (pintype "passive"))
      (node (ref "R16") (pin "1") (pinfunction "1_1") (pintype "passive"))
      (node (ref "U1") (pin "13") (pinfunction "VDDA_13") (pintype "bidirectional"))
    )
    (net (code "44") (name "Net-(U1-VREFH)") (class "Default")
      (node (ref "C11") (pin "1") (pinfunction "1_1") (pintype "passive"))
      (node (ref "R16") (pin "2") (pinfunction "2_2") (pintype "passive"))
      (node (ref "U1") (pin "14") (pinfunction "VREFH_14") (pintype "bidirectional"))
    )
    (net (code "45") (name "Net-(U1-VREFL)") (class "Default")
      (node (ref "C11") (pin "2") (pinfunction "2_2") (pintype "passive"))
      (node (ref "C16") (pin "2") (pinfunction "2_2") (pintype "passive"))
      (node (ref "C17") (pin "2") (pinfunction "2_2") (pintype "passive"))
      (node (ref "L4") (pin "2") (pinfunction "2_2") (pintype "passive"))
      (node (ref "U1") (pin "15") (pinfunction "VREFL_15") (pintype "bidirectional"))
      (node (ref "U1") (pin "16") (pinfunction "VSSA_16") (pintype "bidirectional"))
    )
    (net (code "46") (name "Net-(U1-VREF_OUT)") (class "Default")
      (node (ref "C16") (pin "1") (pinfunction "1_1") (pintype "passive"))
      (node (ref "U1") (pin "17") (pinfunction "VREF_OUT_17") (pintype "bidirectional"))
    )
    (net (code "47") (name "Net-(U1-XTAL32)") (class "Default")
      (node (ref "C31") (pin "2") (pinfunction "2_2") (pintype "passive"))
      (node (ref "U1") (pin "19") (pinfunction "XTAL32_19") (pintype "bidirectional"))
      (node (ref "Y1") (pin "P$2") (pinfunction "2_P$2") (pintype "passive"))
    )
    (net (code "48") (name "Net-(U2-FB)") (class "Default")
      (node (ref "R6") (pin "2") (pinfunction "2_2") (pintype "passive"))
      (node (ref "R7") (pin "1") (pinfunction "1_1") (pintype "passive"))
      (node (ref "U2") (pin "10") (pinfunction "FB_10") (pintype "passive"))
    )
    (net (code "49") (name "Net-(U2-L)") (class "Default")
      (node (ref "L1") (pin "1") (pinfunction "1_1") (pintype "passive"))
      (node (ref "U2") (pin "3") (pinfunction "L_3") (pintype "passive"))
    )
    (net (code "50") (name "Net-(U2-UVLO)") (class "Default")
      (node (ref "C2") (pin "2") (pinfunction "2_2") (pintype "passive"))
      (node (ref "R3") (pin "1") (pinfunction "1_1") (pintype "passive"))
      (node (ref "R4") (pin "2") (pinfunction "2_2") (pintype "passive"))
      (node (ref "U2") (pin "7") (pinfunction "UVLO_7") (pintype "passive"))
    )
    (net (code "51") (name "Net-(U2-VAUX)") (class "Default")
      (node (ref "C4") (pin "1") (pinfunction "1_1") (pintype "passive"))
      (node (ref "U2") (pin "1") (pinfunction "VAUX_1") (pintype "passive"))
    )
    (net (code "52") (name "Net-(U3-REGOUT)") (class "Default")
      (node (ref "C27") (pin "2") (pinfunction "2_2") (pintype "passive"))
      (node (ref "U3") (pin "10") (pinfunction "REGOUT_10") (pintype "bidirectional"))
    )
    (net (code "53") (name "Net-(Y3-2)") (class "Default")
      (node (ref "C23") (pin "1") (pinfunction "1_1") (pintype "passive"))
      (node (ref "U$6") (pin "XTAL_IN/28") (pinfunction "XTAL_IN/28_XTAL_IN/28") (pintype "bidirectional"))
      (node (ref "Y3") (pin "3") (pinfunction "2_3") (pintype "passive"))
    )
    (net (code "54") (name "PS") (class "Default")
      (node (ref "R2") (pin "2") (pinfunction "2_2") (pintype "passive"))
      (node (ref "U2") (pin "8") (pinfunction "PS_8") (pintype "input"))
    )
    (net (code "55") (name "PTA0") (class "Default")
      (node (ref "U$22") (pin "32") (pinfunction "P0.7_32") (pintype "bidirectional"))
      (node (ref "U1") (pin "22") (pinfunction "PTA0_22") (pintype "bidirectional"))
    )
    (net (code "56") (name "PTA3") (class "Default")
      (node (ref "U$22") (pin "33") (pinfunction "P0.6_33") (pintype "bidirectional"))
      (node (ref "U$22") (pin "34") (pinfunction "P0.5_34") (pintype "bidirectional"))
      (node (ref "U1") (pin "25") (pinfunction "PTA3_25") (pintype "bidirectional"))
    )
    (net (code "57") (name "PTB0") (class "Default")
      (node (ref "U1") (pin "35") (pinfunction "PTB0_35") (pintype "bidirectional"))
      (node (ref "U3") (pin "12") (pinfunction "INT_12") (pintype "bidirectional"))
    )
    (net (code "58") (name "PTB1") (class "Default")
      (node (ref "U1") (pin "36") (pinfunction "PTB1_36") (pintype "bidirectional"))
      (node (ref "U3") (pin "11") (pinfunction "FSYNC_11") (pintype "bidirectional"))
    )
    (net (code "59") (name "PTB16") (class "Default")
      (node (ref "U$6") (pin "U0TXD/26") (pinfunction "U0TXD/26_U0TXD/26") (pintype "bidirectional"))
      (node (ref "U1") (pin "39") (pinfunction "PTB16_39") (pintype "bidirectional"))
    )
    (net (code "60") (name "PTB17") (class "Default")
      (node (ref "U$6") (pin "U0RXD/25") (pinfunction "U0RXD/25_U0RXD/25") (pintype "bidirectional"))
      (node (ref "U1") (pin "40") (pinfunction "PTB17_40") (pintype "bidirectional"))
    )
    (net (code "61") (name "PTB18") (class "Default")
      (node (ref "U$6") (pin "GPIO0/15") (pinfunction "GPIO0/15_GPIO0/15") (pintype "bidirectional"))
      (node (ref "U1") (pin "41") (pinfunction "PTB18_41") (pintype "bidirectional"))
    )
    (net (code "62") (name "PTB19") (class "Default")
      (node (ref "U$6") (pin "GPIO2/14") (pinfunction "GPIO2/14_GPIO2/14") (pintype "bidirectional"))
      (node (ref "U1") (pin "42") (pinfunction "PTB19_42") (pintype "bidirectional"))
    )
    (net (code "63") (name "PTC0") (class "Default")
      (node (ref "R15") (pin "1") (pinfunction "1_1") (pintype "passive"))
      (node (ref "U$6") (pin "EXT_RSTB/32") (pinfunction "EXT_RSTB/32_EXT_RSTB/32") (pintype "bidirectional"))
      (node (ref "U1") (pin "43") (pinfunction "PTC0_43") (pintype "bidirectional"))
    )
    (net (code "64") (name "PTC1") (class "Default")
      (node (ref "U$6") (pin "CHIP_EN/7") (pinfunction "CHIP_EN/7_CHIP_EN/7") (pintype "bidirectional"))
      (node (ref "U1") (pin "44") (pinfunction "PTC1_44") (pintype "bidirectional"))
    )
    (net (code "65") (name "PTC3") (class "Default")
      (node (ref "U$6") (pin "XPD_DCDC/8") (pinfunction "XPD_DCDC/8_XPD_DCDC/8") (pintype "bidirectional"))
      (node (ref "U1") (pin "46") (pinfunction "PTC3_46") (pintype "bidirectional"))
    )
    (net (code "66") (name "PTC4") (class "Default")
      (node (ref "U$4") (pin "2") (pinfunction "CSN/2_2") (pintype "bidirectional"))
      (node (ref "U1") (pin "49") (pinfunction "PTC4_49") (pintype "bidirectional"))
    )
    (net (code "67") (name "PTC5") (class "Default")
      (node (ref "U$4") (pin "3") (pinfunction "SCK/3_3") (pintype "bidirectional"))
      (node (ref "U1") (pin "50") (pinfunction "PTC5_50") (pintype "bidirectional"))
    )
    (net (code "68") (name "PTC6") (class "Default")
      (node (ref "U$4") (pin "4") (pinfunction "MOSI/4_4") (pintype "bidirectional"))
      (node (ref "U1") (pin "51") (pinfunction "PTC6_51") (pintype "bidirectional"))
    )
    (net (code "69") (name "PTC7") (class "Default")
      (node (ref "U$4") (pin "5") (pinfunction "MISO/5_5") (pintype "bidirectional"))
      (node (ref "U1") (pin "52") (pinfunction "PTC7_52") (pintype "bidirectional"))
    )
    (net (code "70") (name "PTC8") (class "Default")
      (node (ref "U$4") (pin "6") (pinfunction "IRQ/6_6") (pintype "bidirectional"))
      (node (ref "U1") (pin "53") (pinfunction "PTC8_53") (pintype "bidirectional"))
    )
    (net (code "71") (name "PTC9") (class "Default")
      (node (ref "U$4") (pin "1") (pinfunction "CE/1_1") (pintype "bidirectional"))
      (node (ref "U1") (pin "54") (pinfunction "PTC9_54") (pintype "bidirectional"))
    )
    (net (code "72") (name "PTC10") (class "Default")
      (node (ref "JP1") (pin "12") (pinfunction "12_12") (pintype "passive"))
      (node (ref "U1") (pin "55") (pinfunction "PTC10_55") (pintype "bidirectional"))
    )
    (net (code "73") (name "PTC11") (class "Default")
      (node (ref "JP1") (pin "11") (pinfunction "11_11") (pintype "passive"))
      (node (ref "U1") (pin "56") (pinfunction "PTC11_56") (pintype "bidirectional"))
    )
    (net (code "74") (name "PTD0") (class "Default")
      (node (ref "JP1") (pin "10") (pinfunction "10_10") (pintype "passive"))
      (node (ref "U1") (pin "57") (pinfunction "PTD0_57") (pintype "bidirectional"))
    )
    (net (code "75") (name "PTD1") (class "Default")
      (node (ref "JP1") (pin "9") (pinfunction "9_9") (pintype "passive"))
      (node (ref "U1") (pin "58") (pinfunction "PTD1_58") (pintype "bidirectional"))
    )
    (net (code "76") (name "PTD2") (class "Default")
      (node (ref "JP1") (pin "8") (pinfunction "8_8") (pintype "passive"))
      (node (ref "U1") (pin "59") (pinfunction "PTD2_59") (pintype "bidirectional"))
    )
    (net (code "77") (name "PTD3") (class "Default")
      (node (ref "JP1") (pin "7") (pinfunction "7_7") (pintype "passive"))
      (node (ref "U1") (pin "60") (pinfunction "PTD3_60") (pintype "bidirectional"))
    )
    (net (code "78") (name "PTD4") (class "Default")
      (node (ref "JP1") (pin "6") (pinfunction "6_6") (pintype "passive"))
      (node (ref "U1") (pin "61") (pinfunction "PTD4_61") (pintype "bidirectional"))
    )
    (net (code "79") (name "PTD5") (class "Default")
      (node (ref "JP1") (pin "5") (pinfunction "5_5") (pintype "passive"))
      (node (ref "U1") (pin "62") (pinfunction "PTD5_62") (pintype "bidirectional"))
    )
    (net (code "80") (name "SCL") (class "Default")
      (node (ref "R14") (pin "2") (pinfunction "2_2") (pintype "passive"))
      (node (ref "U1") (pin "37") (pinfunction "PTB2_37") (pintype "bidirectional"))
      (node (ref "U3") (pin "23") (pinfunction "SCLK_23") (pintype "bidirectional"))
    )
    (net (code "81") (name "SDA") (class "Default")
      (node (ref "R13") (pin "2") (pinfunction "2_2") (pintype "passive"))
      (node (ref "U1") (pin "38") (pinfunction "PTB3_38") (pintype "bidirectional"))
      (node (ref "U3") (pin "24") (pinfunction "SDA/MOSI_24") (pintype "bidirectional"))
    )
    (net (code "82") (name "SOFTPOWER") (class "Default")
      (node (ref "R10") (pin "1") (pinfunction "1_1") (pintype "passive"))
      (node (ref "U2") (pin "6") (pinfunction "EN_6") (pintype "input"))
    )
    (net (code "83") (name "USB_D_P") (class "Default")
      (node (ref "R20") (pin "2") (pinfunction "2_2") (pintype "passive"))
      (node (ref "U1") (pin "6") (pinfunction "USB0_DM_6") (pintype "bidirectional"))
    )
    (net (code "84") (name "VCC") (class "Default")
      (node (ref "C1") (pin "1") (pinfunction "1_1") (pintype "passive"))
      (node (ref "C2") (pin "1") (pinfunction "1_1") (pintype "passive"))
      (node (ref "L1") (pin "2") (pinfunction "2_2") (pintype "passive"))
      (node (ref "R10") (pin "2") (pinfunction "2_2") (pintype "passive"))
      (node (ref "R2") (pin "1") (pinfunction "1_1") (pintype "passive"))
      (node (ref "R3") (pin "2") (pinfunction "2_2") (pintype "passive"))
      (node (ref "S1") (pin "2") (pinfunction "P_2") (pintype "passive"))
      (node (ref "U2") (pin "5") (pinfunction "VIN_5") (pintype "power_in"))
    )
    (net (code "85") (name "VUSB") (class "Default")
      (node (ref "J1") (pin "1") (pinfunction "+5V_1") (pintype "bidirectional"))
      (node (ref "S1") (pin "1") (pinfunction "O_1") (pintype "passive"))
    )
    (net (code "86") (name "unconnected-(L9-Pad2)") (class "Default")
      (node (ref "L9") (pin "2") (pinfunction "2_2") (pintype "passive"))
    )
    (net (code "87") (name "unconnected-(U$6-PadDVDD{slash}24)") (class "Default")
      (node (ref "U$6") (pin "DVDD/24") (pinfunction "DVDD/24_DVDD/24") (pintype "bidirectional"))
    )
    (net (code "88") (name "unconnected-(U$6-PadMTDI{slash}10)") (class "Default")
      (node (ref "U$6") (pin "MTDI/10") (pinfunction "MTDI/10_MTDI/10") (pintype "bidirectional"))
    )
    (net (code "89") (name "unconnected-(U$6-PadMTMS{slash}9)") (class "Default")
      (node (ref "U$6") (pin "MTMS/9") (pinfunction "MTMS/9_MTMS/9") (pintype "bidirectional"))
    )
    (net (code "90") (name "unconnected-(U$6-PadTOUT{slash}6)") (class "Default")
      (node (ref "U$6") (pin "TOUT/6") (pinfunction "TOUT/6_TOUT/6") (pintype "bidirectional"))
    )
    (net (code "91") (name "unconnected-(U$6-PadVDD_RTC{slash}5)") (class "Default")
      (node (ref "U$6") (pin "VDD_RTC/5") (pinfunction "VDD_RTC/5_VDD_RTC/5") (pintype "bidirectional"))
    )
    (net (code "92") (name "unconnected-(U$6-PadVDD{slash}16)") (class "Default")
      (node (ref "U$6") (pin "VDD/16") (pinfunction "VDD/16_VDD/16") (pintype "bidirectional"))
    )
    (net (code "93") (name "unconnected-(U$22-P3.4-Pad9)") (class "Default")
      (node (ref "U$22") (pin "9") (pinfunction "P3.4_9") (pintype "bidirectional"))
    )
    (net (code "94") (name "unconnected-(U$22-P3.5-Pad10)") (class "Default")
      (node (ref "U$22") (pin "10") (pinfunction "P3.5_10") (pintype "bidirectional"))
    )
    (net (code "95") (name "unconnected-(U1-ADC0_DM0-Pad10)") (class "Default")
      (node (ref "U1") (pin "10") (pinfunction "ADC0_DM0_10") (pintype "bidirectional"))
    )
    (net (code "96") (name "unconnected-(U1-ADC0_DM3-Pad12)") (class "Default")
      (node (ref "U1") (pin "12") (pinfunction "ADC0_DM3_12") (pintype "bidirectional"))
    )
    (net (code "97") (name "unconnected-(U1-ADC0_DP0-Pad9)") (class "Default")
      (node (ref "U1") (pin "9") (pinfunction "ADC0_DP0_9") (pintype "bidirectional"))
    )
    (net (code "98") (name "unconnected-(U1-ADC0_DP3-Pad11)") (class "Default")
      (node (ref "U1") (pin "11") (pinfunction "ADC0_DP3_11") (pintype "bidirectional"))
    )
    (net (code "99") (name "unconnected-(U1-DAC0-Pad18)") (class "Default")
      (node (ref "U1") (pin "18") (pinfunction "DAC0_18") (pintype "bidirectional"))
    )
    (net (code "100") (name "unconnected-(U1-PTA4-Pad26)") (class "Default")
      (node (ref "U1") (pin "26") (pinfunction "PTA4_26") (pintype "bidirectional"))
    )
    (net (code "101") (name "unconnected-(U1-PTA5-Pad27)") (class "Default")
      (node (ref "U1") (pin "27") (pinfunction "PTA5_27") (pintype "bidirectional"))
    )
    (net (code "102") (name "unconnected-(U1-PTA12-Pad28)") (class "Default")
      (node (ref "U1") (pin "28") (pinfunction "PTA12_28") (pintype "bidirectional"))
    )
    (net (code "103") (name "unconnected-(U1-PTA13-Pad29)") (class "Default")
      (node (ref "U1") (pin "29") (pinfunction "PTA13_29") (pintype "bidirectional"))
    )
    (net (code "104") (name "unconnected-(U1-PTE0-Pad1)") (class "Default")
      (node (ref "U1") (pin "1") (pinfunction "PTE0_1") (pintype "bidirectional"))
    )
    (net (code "105") (name "unconnected-(U1-PTE1-Pad2)") (class "Default")
      (node (ref "U1") (pin "2") (pinfunction "PTE1_2") (pintype "bidirectional"))
    )
    (net (code "106") (name "unconnected-(U3-AUX_CL-Pad7)") (class "Default")
      (node (ref "U3") (pin "7") (pinfunction "AUX_CL_7") (pintype "bidirectional"))
    )
    (net (code "107") (name "unconnected-(U3-AUX_DA-Pad21)") (class "Default")
      (node (ref "U3") (pin "21") (pinfunction "AUX_DA_21") (pintype "bidirectional"))
    )
  )
)
